# EsquematicoMicro.net
KiCad netlist of a schematic drawn in EAGLE
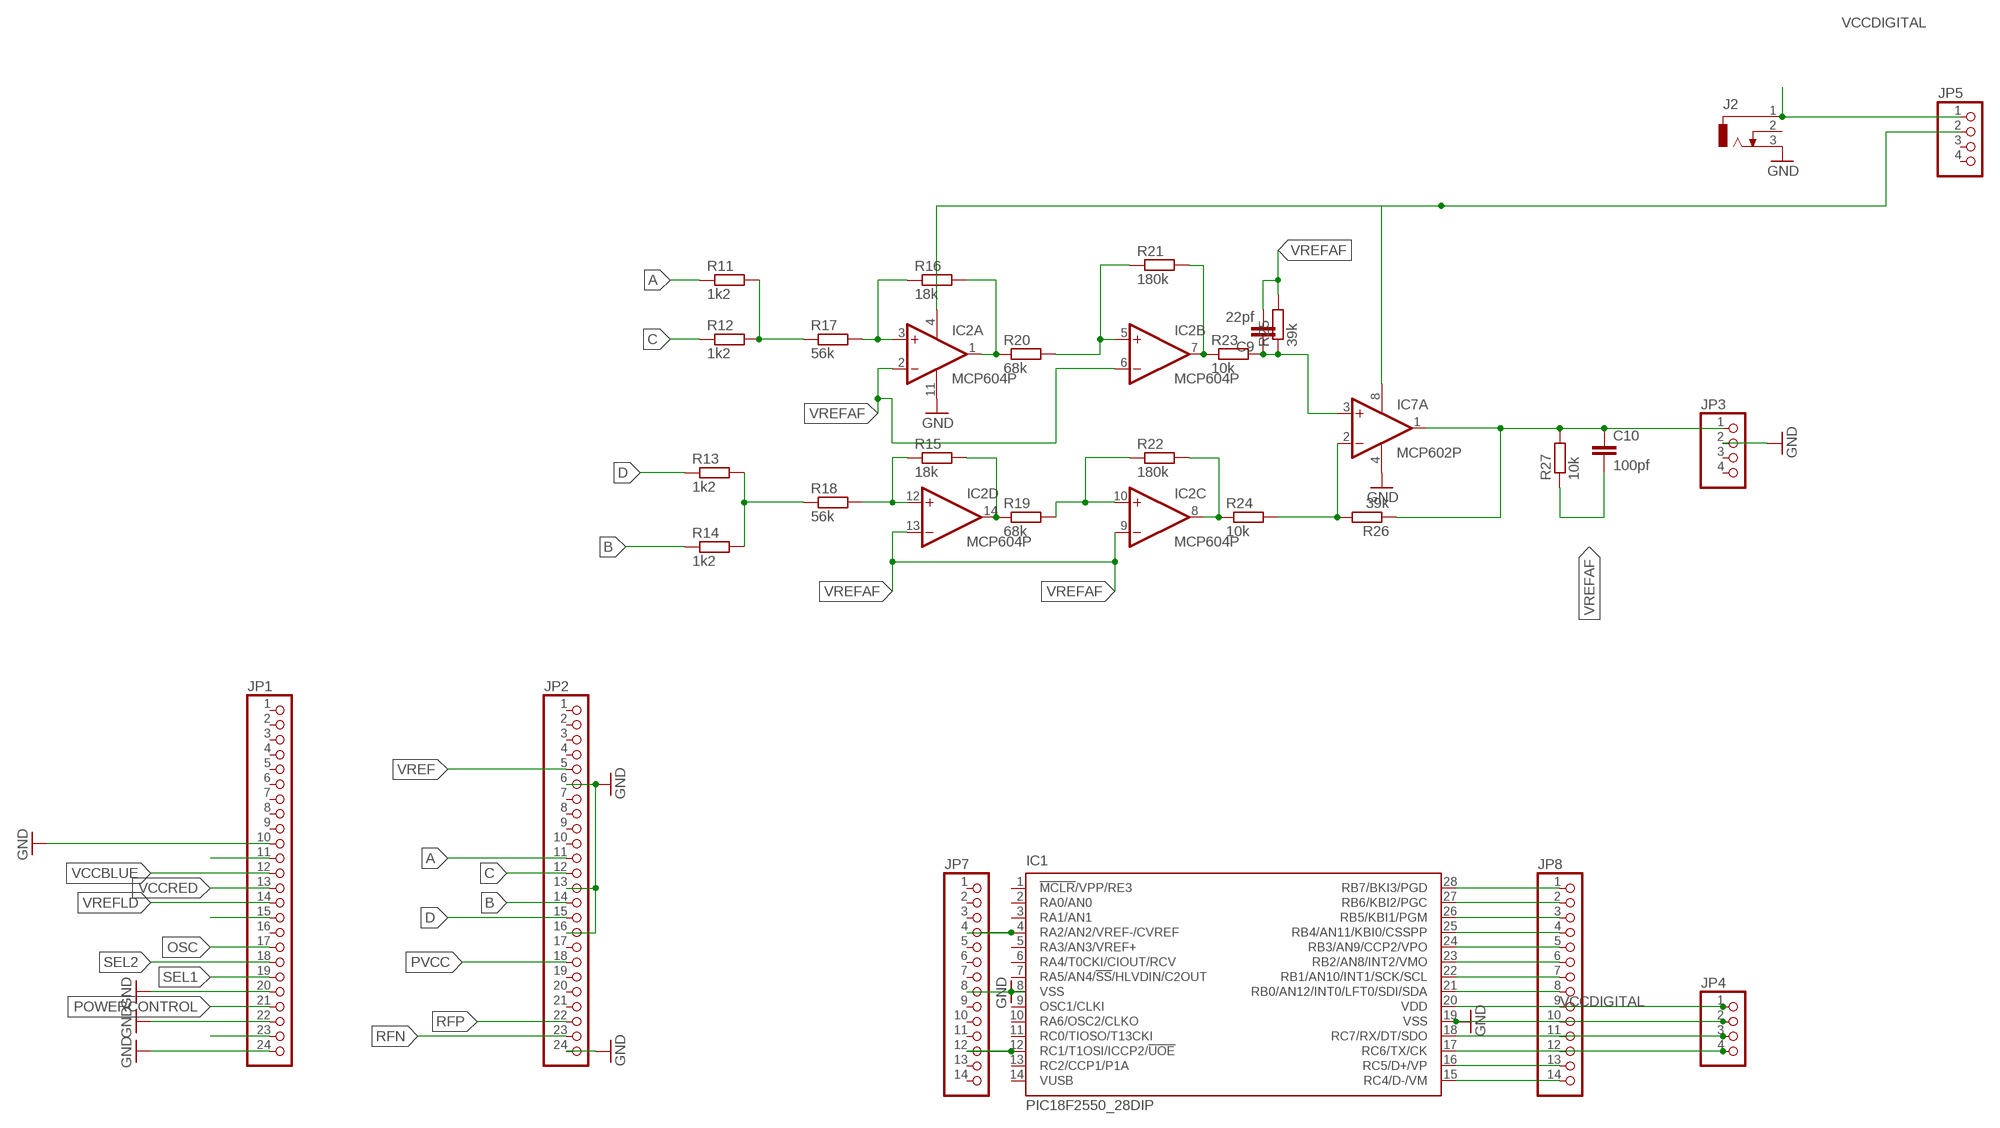
[diagram p0: schematic, sheet 1]

(export (version "E")
  (design (tool "Eeschema 10.0.6"))
  (components
    (comp (ref "C9")
      (value "22pf")
      (footprint "eagle-import:C025-025X050")
      (libsource (lib "eagle-import") (part "C-EU025-025X050"))
    )
    (comp (ref "C10")
      (value "100pf")
      (footprint "eagle-import:C025-025X050")
      (libsource (lib "eagle-import") (part "C-EU025-025X050"))
    )
    (comp (ref "IC1")
      (value "PIC18F2550_28DIP")
      (footprint "eagle-import:DIL28-3")
      (fields (field (name "MF") "MICROCHIP") (field (name "MPN") "PIC18F2550-I/SP"))
      (libsource (lib "eagle-import") (part "PIC18F2_28DIP550"))
    )
    (comp (ref "IC2")
      (value "MCP604P")
      (footprint "eagle-import:DIL14")
      (libsource (lib "eagle-import") (part "MCP604P"))
    )
    (comp (ref "IC7")
      (value "MCP602P")
      (footprint "eagle-import:DIL08")
      (fields (field (name "SPICEPREFIX") "I"))
      (libsource (lib "eagle-import") (part "MCP602P"))
    )
    (comp (ref "J2")
      (value "DCJ0303")
      (footprint "eagle-import:DCJ0303")
      (libsource (lib "eagle-import") (part "DCJ0303"))
    )
    (comp (ref "JP1")
      (value "PINHD-1X24")
      (footprint "eagle-import:1X24")
      (libsource (lib "eagle-import") (part "PINHD-1X24"))
    )
    (comp (ref "JP2")
      (value "PINHD-1X24")
      (footprint "eagle-import:1X24")
      (libsource (lib "eagle-import") (part "PINHD-1X24"))
    )
    (comp (ref "JP3")
      (value "PINHD-1X4")
      (footprint "eagle-import:1X04")
      (libsource (lib "eagle-import") (part "PINHD-1X4"))
    )
    (comp (ref "JP4")
      (value "PINHD-1X4")
      (footprint "eagle-import:1X04")
      (libsource (lib "eagle-import") (part "PINHD-1X4"))
    )
    (comp (ref "JP5")
      (value "PINHD-1X4")
      (footprint "eagle-import:1X04")
      (libsource (lib "eagle-import") (part "PINHD-1X4"))
    )
    (comp (ref "JP7")
      (value "PINHD-1X14")
      (footprint "eagle-import:1X14")
      (libsource (lib "eagle-import") (part "PINHD-1X14"))
    )
    (comp (ref "JP8")
      (value "PINHD-1X14")
      (footprint "eagle-import:1X14")
      (libsource (lib "eagle-import") (part "PINHD-1X14"))
    )
    (comp (ref "R11")
      (value "1k2")
      (footprint "eagle-import:0204_5")
      (libsource (lib "eagle-import") (part "R-EU_0204/5"))
    )
    (comp (ref "R12")
      (value "1k2")
      (footprint "eagle-import:0204_5")
      (libsource (lib "eagle-import") (part "R-EU_0204/5"))
    )
    (comp (ref "R13")
      (value "1k2")
      (footprint "eagle-import:0204_5")
      (libsource (lib "eagle-import") (part "R-EU_0204/5"))
    )
    (comp (ref "R14")
      (value "1k2")
      (footprint "eagle-import:0204_5")
      (libsource (lib "eagle-import") (part "R-EU_0204/5"))
    )
    (comp (ref "R15")
      (value "18k")
      (footprint "eagle-import:0204_5")
      (libsource (lib "eagle-import") (part "R-EU_0204/5"))
    )
    (comp (ref "R16")
      (value "18k")
      (footprint "eagle-import:0204_5")
      (libsource (lib "eagle-import") (part "R-EU_0204/5"))
    )
    (comp (ref "R17")
      (value "56k")
      (footprint "eagle-import:0204_5")
      (libsource (lib "eagle-import") (part "R-EU_0204/5"))
    )
    (comp (ref "R18")
      (value "56k")
      (footprint "eagle-import:0204_5")
      (libsource (lib "eagle-import") (part "R-EU_0204/5"))
    )
    (comp (ref "R19")
      (value "68k")
      (footprint "eagle-import:0204_5")
      (libsource (lib "eagle-import") (part "R-EU_0204/5"))
    )
    (comp (ref "R20")
      (value "68k")
      (footprint "eagle-import:0204_5")
      (libsource (lib "eagle-import") (part "R-EU_0204/5"))
    )
    (comp (ref "R21")
      (value "180k")
      (footprint "eagle-import:0204_5")
      (libsource (lib "eagle-import") (part "R-EU_0204/5"))
    )
    (comp (ref "R22")
      (value "180k")
      (footprint "eagle-import:0204_5")
      (libsource (lib "eagle-import") (part "R-EU_0204/5"))
    )
    (comp (ref "R23")
      (value "10k")
      (footprint "eagle-import:0204_5")
      (libsource (lib "eagle-import") (part "R-EU_0204/5"))
    )
    (comp (ref "R24")
      (value "10k")
      (footprint "eagle-import:0204_5")
      (libsource (lib "eagle-import") (part "R-EU_0204/5"))
    )
    (comp (ref "R25")
      (value "39k")
      (footprint "eagle-import:0204_5")
      (libsource (lib "eagle-import") (part "R-EU_0204/5"))
    )
    (comp (ref "R26")
      (value "39k")
      (footprint "eagle-import:0204_5")
      (libsource (lib "eagle-import") (part "R-EU_0204/5"))
    )
    (comp (ref "R27")
      (value "10k")
      (footprint "eagle-import:0204_5")
      (libsource (lib "eagle-import") (part "R-EU_0204/5"))
    )
  )
  (nets
    (net (code "1") (name "/VCCDIGITAL") (class "Default")
      (node (ref "IC1") (pin "20") (pinfunction "VDD_20") (pintype "power_in"))
      (node (ref "J2") (pin "1") (pinfunction "1_1") (pintype "passive"))
      (node (ref "JP4") (pin "1") (pinfunction "1_1") (pintype "passive"))
      (node (ref "JP5") (pin "1") (pinfunction "1_1") (pintype "passive"))
      (node (ref "JP8") (pin "9") (pinfunction "9_9") (pintype "passive"))
    )
    (net (code "2") (name "A") (class "Default")
      (node (ref "JP2") (pin "11") (pinfunction "11_11") (pintype "passive"))
      (node (ref "R11") (pin "1") (pinfunction "1_1") (pintype "passive"))
    )
    (net (code "3") (name "B") (class "Default")
      (node (ref "JP2") (pin "14") (pinfunction "14_14") (pintype "passive"))
      (node (ref "R14") (pin "1") (pinfunction "1_1") (pintype "passive"))
    )
    (net (code "4") (name "C") (class "Default")
      (node (ref "JP2") (pin "12") (pinfunction "12_12") (pintype "passive"))
      (node (ref "R12") (pin "1") (pinfunction "1_1") (pintype "passive"))
    )
    (net (code "5") (name "D") (class "Default")
      (node (ref "JP2") (pin "15") (pinfunction "15_15") (pintype "passive"))
      (node (ref "R13") (pin "1") (pinfunction "1_1") (pintype "passive"))
    )
    (net (code "6") (name "GND") (class "Default")
      (node (ref "IC1") (pin "19") (pinfunction "VSS_19") (pintype "power_in"))
      (node (ref "IC1") (pin "8") (pinfunction "VSS_8") (pintype "power_in"))
      (node (ref "IC2") (pin "11") (pinfunction "V-_11") (pintype "power_in"))
      (node (ref "IC7") (pin "4") (pinfunction "V-_4") (pintype "power_in"))
      (node (ref "J2") (pin "3") (pinfunction "3_3") (pintype "passive"))
      (node (ref "JP1") (pin "10") (pinfunction "10_10") (pintype "passive"))
      (node (ref "JP1") (pin "20") (pinfunction "20_20") (pintype "passive"))
      (node (ref "JP1") (pin "22") (pinfunction "22_22") (pintype "passive"))
      (node (ref "JP1") (pin "24") (pinfunction "24_24") (pintype "passive"))
      (node (ref "JP2") (pin "13") (pinfunction "13_13") (pintype "passive"))
      (node (ref "JP2") (pin "16") (pinfunction "16_16") (pintype "passive"))
      (node (ref "JP2") (pin "24") (pinfunction "24_24") (pintype "passive"))
      (node (ref "JP2") (pin "6") (pinfunction "6_6") (pintype "passive"))
      (node (ref "JP3") (pin "2") (pinfunction "2_2") (pintype "passive"))
      (node (ref "JP4") (pin "2") (pinfunction "2_2") (pintype "passive"))
      (node (ref "JP7") (pin "8") (pinfunction "8_8") (pintype "passive"))
      (node (ref "JP8") (pin "10") (pinfunction "10_10") (pintype "passive"))
    )
    (net (code "7") (name "Net-(IC1-RA2{slash}AN2{slash}VREF-{slash}CVREF)") (class "Default")
      (node (ref "IC1") (pin "4") (pinfunction "RA2/AN2/VREF-/CVREF_4") (pintype "bidirectional"))
      (node (ref "JP7") (pin "4") (pinfunction "4_4") (pintype "passive"))
    )
    (net (code "8") (name "Net-(IC1-RB0{slash}AN12{slash}INT0{slash}LFT0{slash}SDI{slash}SDA)") (class "Default")
      (node (ref "IC1") (pin "21") (pinfunction "RB0/AN12/INT0/LFT0/SDI/SDA_21") (pintype "bidirectional"))
      (node (ref "JP8") (pin "8") (pinfunction "8_8") (pintype "passive"))
    )
    (net (code "9") (name "Net-(IC1-RB1{slash}AN10{slash}INT1{slash}SCK{slash}SCL)") (class "Default")
      (node (ref "IC1") (pin "22") (pinfunction "RB1/AN10/INT1/SCK/SCL_22") (pintype "bidirectional"))
      (node (ref "JP8") (pin "7") (pinfunction "7_7") (pintype "passive"))
    )
    (net (code "10") (name "Net-(IC1-RB2{slash}AN8{slash}INT2{slash}VMO)") (class "Default")
      (node (ref "IC1") (pin "23") (pinfunction "RB2/AN8/INT2/VMO_23") (pintype "bidirectional"))
      (node (ref "JP8") (pin "6") (pinfunction "6_6") (pintype "passive"))
    )
    (net (code "11") (name "Net-(IC1-RB3{slash}AN9{slash}CCP2{slash}VPO)") (class "Default")
      (node (ref "IC1") (pin "24") (pinfunction "RB3/AN9/CCP2/VPO_24") (pintype "bidirectional"))
      (node (ref "JP8") (pin "5") (pinfunction "5_5") (pintype "passive"))
    )
    (net (code "12") (name "Net-(IC1-RB4{slash}AN11{slash}KBI0{slash}CSSPP)") (class "Default")
      (node (ref "IC1") (pin "25") (pinfunction "RB4/AN11/KBI0/CSSPP_25") (pintype "bidirectional"))
      (node (ref "JP8") (pin "4") (pinfunction "4_4") (pintype "passive"))
    )
    (net (code "13") (name "Net-(IC1-RB5{slash}KBI1{slash}PGM)") (class "Default")
      (node (ref "IC1") (pin "26") (pinfunction "RB5/KBI1/PGM_26") (pintype "bidirectional"))
      (node (ref "JP8") (pin "3") (pinfunction "3_3") (pintype "passive"))
    )
    (net (code "14") (name "Net-(IC1-RB6{slash}KBI2{slash}PGC)") (class "Default")
      (node (ref "IC1") (pin "27") (pinfunction "RB6/KBI2/PGC_27") (pintype "bidirectional"))
      (node (ref "JP8") (pin "2") (pinfunction "2_2") (pintype "passive"))
    )
    (net (code "15") (name "Net-(IC1-RB7{slash}BKI3{slash}PGD)") (class "Default")
      (node (ref "IC1") (pin "28") (pinfunction "RB7/BKI3/PGD_28") (pintype "bidirectional"))
      (node (ref "JP8") (pin "1") (pinfunction "1_1") (pintype "passive"))
    )
    (net (code "16") (name "Net-(IC1-RC1{slash}T1OSI{slash}ICCP2{slash}~{UOE})") (class "Default")
      (node (ref "IC1") (pin "12") (pinfunction "RC1/T1OSI/ICCP2/~{UOE}_12") (pintype "bidirectional"))
      (node (ref "JP7") (pin "12") (pinfunction "12_12") (pintype "passive"))
    )
    (net (code "17") (name "Net-(IC1-RC4{slash}D-{slash}VM)") (class "Default")
      (node (ref "IC1") (pin "15") (pinfunction "RC4/D-/VM_15") (pintype "bidirectional"))
      (node (ref "JP8") (pin "14") (pinfunction "14_14") (pintype "passive"))
    )
    (net (code "18") (name "Net-(IC1-RC5{slash}D+{slash}VP)") (class "Default")
      (node (ref "IC1") (pin "16") (pinfunction "RC5/D+/VP_16") (pintype "bidirectional"))
      (node (ref "JP8") (pin "13") (pinfunction "13_13") (pintype "passive"))
    )
    (net (code "19") (name "Net-(IC1-RC6{slash}TX{slash}CK)") (class "Default")
      (node (ref "IC1") (pin "17") (pinfunction "RC6/TX/CK_17") (pintype "bidirectional"))
      (node (ref "JP4") (pin "4") (pinfunction "4_4") (pintype "passive"))
      (node (ref "JP8") (pin "12") (pinfunction "12_12") (pintype "passive"))
    )
    (net (code "20") (name "Net-(IC1-RC7{slash}RX{slash}DT{slash}SDO)") (class "Default")
      (node (ref "IC1") (pin "18") (pinfunction "RC7/RX/DT/SDO_18") (pintype "bidirectional"))
      (node (ref "JP4") (pin "3") (pinfunction "3_3") (pintype "passive"))
      (node (ref "JP8") (pin "11") (pinfunction "11_11") (pintype "passive"))
    )
    (net (code "21") (name "Net-(IC2A-+IN)") (class "Default")
      (node (ref "IC2") (pin "3") (pinfunction "+IN_3") (pintype "input"))
      (node (ref "R16") (pin "1") (pinfunction "1_1") (pintype "passive"))
      (node (ref "R17") (pin "2") (pinfunction "2_2") (pintype "passive"))
    )
    (net (code "22") (name "Net-(IC2A-OUT)") (class "Default")
      (node (ref "IC2") (pin "1") (pinfunction "OUT_1") (pintype "output"))
      (node (ref "R16") (pin "2") (pinfunction "2_2") (pintype "passive"))
      (node (ref "R20") (pin "1") (pinfunction "1_1") (pintype "passive"))
    )
    (net (code "23") (name "Net-(IC2B-+IN)") (class "Default")
      (node (ref "IC2") (pin "5") (pinfunction "+IN_5") (pintype "input"))
      (node (ref "R20") (pin "2") (pinfunction "2_2") (pintype "passive"))
      (node (ref "R21") (pin "1") (pinfunction "1_1") (pintype "passive"))
    )
    (net (code "24") (name "Net-(IC2B-OUT)") (class "Default")
      (node (ref "IC2") (pin "7") (pinfunction "OUT_7") (pintype "output"))
      (node (ref "R21") (pin "2") (pinfunction "2_2") (pintype "passive"))
      (node (ref "R23") (pin "1") (pinfunction "1_1") (pintype "passive"))
    )
    (net (code "25") (name "Net-(IC2C-+IN)") (class "Default")
      (node (ref "IC2") (pin "10") (pinfunction "+IN_10") (pintype "input"))
      (node (ref "R19") (pin "2") (pinfunction "2_2") (pintype "passive"))
      (node (ref "R22") (pin "1") (pinfunction "1_1") (pintype "passive"))
    )
    (net (code "26") (name "Net-(IC2C-OUT)") (class "Default")
      (node (ref "IC2") (pin "8") (pinfunction "OUT_8") (pintype "output"))
      (node (ref "R22") (pin "2") (pinfunction "2_2") (pintype "passive"))
      (node (ref "R24") (pin "1") (pinfunction "1_1") (pintype "passive"))
    )
    (net (code "27") (name "Net-(IC2D-+IN)") (class "Default")
      (node (ref "IC2") (pin "12") (pinfunction "+IN_12") (pintype "input"))
      (node (ref "R15") (pin "1") (pinfunction "1_1") (pintype "passive"))
      (node (ref "R18") (pin "2") (pinfunction "2_2") (pintype "passive"))
    )
    (net (code "28") (name "Net-(IC2D-OUT)") (class "Default")
      (node (ref "IC2") (pin "14") (pinfunction "OUT_14") (pintype "output"))
      (node (ref "R15") (pin "2") (pinfunction "2_2") (pintype "passive"))
      (node (ref "R19") (pin "1") (pinfunction "1_1") (pintype "passive"))
    )
    (net (code "29") (name "Net-(IC2E-V+)") (class "Default")
      (node (ref "IC2") (pin "4") (pinfunction "V+_4") (pintype "power_in"))
      (node (ref "IC7") (pin "8") (pinfunction "V+_8") (pintype "power_in"))
      (node (ref "JP5") (pin "2") (pinfunction "2_2") (pintype "passive"))
    )
    (net (code "30") (name "Net-(IC7A-+IN)") (class "Default")
      (node (ref "C9") (pin "1") (pinfunction "1_1") (pintype "passive"))
      (node (ref "IC7") (pin "3") (pinfunction "+IN_3") (pintype "input"))
      (node (ref "R23") (pin "2") (pinfunction "2_2") (pintype "passive"))
      (node (ref "R25") (pin "1") (pinfunction "1_1") (pintype "passive"))
    )
    (net (code "31") (name "Net-(IC7A--IN)") (class "Default")
      (node (ref "IC7") (pin "2") (pinfunction "-IN_2") (pintype "input"))
      (node (ref "R24") (pin "2") (pinfunction "2_2") (pintype "passive"))
      (node (ref "R26") (pin "2") (pinfunction "2_2") (pintype "passive"))
    )
    (net (code "32") (name "Net-(IC7A-OUT)") (class "Default")
      (node (ref "C10") (pin "1") (pinfunction "1_1") (pintype "passive"))
      (node (ref "IC7") (pin "1") (pinfunction "OUT_1") (pintype "output"))
      (node (ref "JP3") (pin "1") (pinfunction "1_1") (pintype "passive"))
      (node (ref "R26") (pin "1") (pinfunction "1_1") (pintype "passive"))
      (node (ref "R27") (pin "2") (pinfunction "2_2") (pintype "passive"))
    )
    (net (code "33") (name "Net-(R11-Pad2)") (class "Default")
      (node (ref "R11") (pin "2") (pinfunction "2_2") (pintype "passive"))
      (node (ref "R12") (pin "2") (pinfunction "2_2") (pintype "passive"))
      (node (ref "R17") (pin "1") (pinfunction "1_1") (pintype "passive"))
    )
    (net (code "34") (name "Net-(R13-Pad2)") (class "Default")
      (node (ref "R13") (pin "2") (pinfunction "2_2") (pintype "passive"))
      (node (ref "R14") (pin "2") (pinfunction "2_2") (pintype "passive"))
      (node (ref "R18") (pin "1") (pinfunction "1_1") (pintype "passive"))
    )
    (net (code "35") (name "OSC") (class "Default")
      (node (ref "JP1") (pin "17") (pinfunction "17_17") (pintype "passive"))
    )
    (net (code "36") (name "POWERCONTROL") (class "Default")
      (node (ref "JP1") (pin "21") (pinfunction "21_21") (pintype "passive"))
    )
    (net (code "37") (name "PVCC") (class "Default")
      (node (ref "JP2") (pin "18") (pinfunction "18_18") (pintype "passive"))
    )
    (net (code "38") (name "RFN") (class "Default")
      (node (ref "JP2") (pin "23") (pinfunction "23_23") (pintype "passive"))
    )
    (net (code "39") (name "RFP") (class "Default")
      (node (ref "JP2") (pin "22") (pinfunction "22_22") (pintype "passive"))
    )
    (net (code "40") (name "SEL1") (class "Default")
      (node (ref "JP1") (pin "19") (pinfunction "19_19") (pintype "passive"))
    )
    (net (code "41") (name "SEL2") (class "Default")
      (node (ref "JP1") (pin "18") (pinfunction "18_18") (pintype "passive"))
    )
    (net (code "42") (name "VCCBLUE") (class "Default")
      (node (ref "JP1") (pin "12") (pinfunction "12_12") (pintype "passive"))
    )
    (net (code "43") (name "VCCRED") (class "Default")
      (node (ref "JP1") (pin "13") (pinfunction "13_13") (pintype "passive"))
    )
    (net (code "44") (name "VREF") (class "Default")
      (node (ref "JP2") (pin "5") (pinfunction "5_5") (pintype "passive"))
    )
    (net (code "45") (name "VREFAF") (class "Default")
      (node (ref "C10") (pin "2") (pinfunction "2_2") (pintype "passive"))
      (node (ref "C9") (pin "2") (pinfunction "2_2") (pintype "passive"))
      (node (ref "IC2") (pin "13") (pinfunction "-IN_13") (pintype "input"))
      (node (ref "IC2") (pin "2") (pinfunction "-IN_2") (pintype "input"))
      (node (ref "IC2") (pin "6") (pinfunction "-IN_6") (pintype "input"))
      (node (ref "IC2") (pin "9") (pinfunction "-IN_9") (pintype "input"))
      (node (ref "R25") (pin "2") (pinfunction "2_2") (pintype "passive"))
      (node (ref "R27") (pin "1") (pinfunction "1_1") (pintype "passive"))
    )
    (net (code "46") (name "VREFLD") (class "Default")
      (node (ref "JP1") (pin "14") (pinfunction "14_14") (pintype "passive"))
    )
    (net (code "47") (name "unconnected-(IC1-OSC1{slash}CLKI-Pad9)") (class "Default")
      (node (ref "IC1") (pin "9") (pinfunction "OSC1/CLKI_9") (pintype "input"))
    )
    (net (code "48") (name "unconnected-(IC1-RA0{slash}AN0-Pad2)") (class "Default")
      (node (ref "IC1") (pin "2") (pinfunction "RA0/AN0_2") (pintype "bidirectional"))
    )
    (net (code "49") (name "unconnected-(IC1-RA1{slash}AN1-Pad3)") (class "Default")
      (node (ref "IC1") (pin "3") (pinfunction "RA1/AN1_3") (pintype "bidirectional"))
    )
    (net (code "50") (name "unconnected-(IC1-RA3{slash}AN3{slash}VREF+-Pad5)") (class "Default")
      (node (ref "IC1") (pin "5") (pinfunction "RA3/AN3/VREF+_5") (pintype "bidirectional"))
    )
    (net (code "51") (name "unconnected-(IC1-RA4{slash}T0CKI{slash}CIOUT{slash}RCV-Pad6)") (class "Default")
      (node (ref "IC1") (pin "6") (pinfunction "RA4/T0CKI/CIOUT/RCV_6") (pintype "bidirectional"))
    )
    (net (code "52") (name "unconnected-(IC1-RA5{slash}AN4{slash}~{SS}{slash}HLVDIN{slash}C2OUT-Pad7)") (class "Default")
      (node (ref "IC1") (pin "7") (pinfunction "RA5/AN4/~{SS}/HLVDIN/C2OUT_7") (pintype "bidirectional"))
    )
    (net (code "53") (name "unconnected-(IC1-RA6{slash}OSC2{slash}CLKO-Pad10)") (class "Default")
      (node (ref "IC1") (pin "10") (pinfunction "RA6/OSC2/CLKO_10") (pintype "output"))
    )
    (net (code "54") (name "unconnected-(IC1-RC0{slash}TIOSO{slash}T13CKI-Pad11)") (class "Default")
      (node (ref "IC1") (pin "11") (pinfunction "RC0/TIOSO/T13CKI_11") (pintype "bidirectional"))
    )
    (net (code "55") (name "unconnected-(IC1-RC2{slash}CCP1{slash}P1A-Pad13)") (class "Default")
      (node (ref "IC1") (pin "13") (pinfunction "RC2/CCP1/P1A_13") (pintype "bidirectional"))
    )
    (net (code "56") (name "unconnected-(IC1-VUSB-Pad14)") (class "Default")
      (node (ref "IC1") (pin "14") (pinfunction "VUSB_14") (pintype "bidirectional"))
    )
    (net (code "57") (name "unconnected-(IC1-~{MCLR}{slash}VPP{slash}RE3-Pad1)") (class "Default")
      (node (ref "IC1") (pin "1") (pinfunction "~{MCLR}/VPP/RE3_1") (pintype "input"))
    )
    (net (code "58") (name "unconnected-(J2-Pad2)") (class "Default")
      (node (ref "J2") (pin "2") (pinfunction "2_2") (pintype "passive"))
    )
    (net (code "59") (name "unconnected-(JP1-Pad1)") (class "Default")
      (node (ref "JP1") (pin "1") (pinfunction "1_1") (pintype "passive"))
    )
    (net (code "60") (name "unconnected-(JP1-Pad2)") (class "Default")
      (node (ref "JP1") (pin "2") (pinfunction "2_2") (pintype "passive"))
    )
    (net (code "61") (name "unconnected-(JP1-Pad3)") (class "Default")
      (node (ref "JP1") (pin "3") (pinfunction "3_3") (pintype "passive"))
    )
    (net (code "62") (name "unconnected-(JP1-Pad4)") (class "Default")
      (node (ref "JP1") (pin "4") (pinfunction "4_4") (pintype "passive"))
    )
    (net (code "63") (name "unconnected-(JP1-Pad5)") (class "Default")
      (node (ref "JP1") (pin "5") (pinfunction "5_5") (pintype "passive"))
    )
    (net (code "64") (name "unconnected-(JP1-Pad6)") (class "Default")
      (node (ref "JP1") (pin "6") (pinfunction "6_6") (pintype "passive"))
    )
    (net (code "65") (name "unconnected-(JP1-Pad7)") (class "Default")
      (node (ref "JP1") (pin "7") (pinfunction "7_7") (pintype "passive"))
    )
    (net (code "66") (name "unconnected-(JP1-Pad8)") (class "Default")
      (node (ref "JP1") (pin "8") (pinfunction "8_8") (pintype "passive"))
    )
    (net (code "67") (name "unconnected-(JP1-Pad9)") (class "Default")
      (node (ref "JP1") (pin "9") (pinfunction "9_9") (pintype "passive"))
    )
    (net (code "68") (name "unconnected-(JP1-Pad11)") (class "Default")
      (node (ref "JP1") (pin "11") (pinfunction "11_11") (pintype "passive"))
    )
    (net (code "69") (name "unconnected-(JP1-Pad15)") (class "Default")
      (node (ref "JP1") (pin "15") (pinfunction "15_15") (pintype "passive"))
    )
    (net (code "70") (name "unconnected-(JP1-Pad16)") (class "Default")
      (node (ref "JP1") (pin "16") (pinfunction "16_16") (pintype "passive"))
    )
    (net (code "71") (name "unconnected-(JP1-Pad23)") (class "Default")
      (node (ref "JP1") (pin "23") (pinfunction "23_23") (pintype "passive"))
    )
    (net (code "72") (name "unconnected-(JP2-Pad1)") (class "Default")
      (node (ref "JP2") (pin "1") (pinfunction "1_1") (pintype "passive"))
    )
    (net (code "73") (name "unconnected-(JP2-Pad2)") (class "Default")
      (node (ref "JP2") (pin "2") (pinfunction "2_2") (pintype "passive"))
    )
    (net (code "74") (name "unconnected-(JP2-Pad3)") (class "Default")
      (node (ref "JP2") (pin "3") (pinfunction "3_3") (pintype "passive"))
    )
    (net (code "75") (name "unconnected-(JP2-Pad4)") (class "Default")
      (node (ref "JP2") (pin "4") (pinfunction "4_4") (pintype "passive"))
    )
    (net (code "76") (name "unconnected-(JP2-Pad7)") (class "Default")
      (node (ref "JP2") (pin "7") (pinfunction "7_7") (pintype "passive"))
    )
    (net (code "77") (name "unconnected-(JP2-Pad8)") (class "Default")
      (node (ref "JP2") (pin "8") (pinfunction "8_8") (pintype "passive"))
    )
    (net (code "78") (name "unconnected-(JP2-Pad9)") (class "Default")
      (node (ref "JP2") (pin "9") (pinfunction "9_9") (pintype "passive"))
    )
    (net (code "79") (name "unconnected-(JP2-Pad10)") (class "Default")
      (node (ref "JP2") (pin "10") (pinfunction "10_10") (pintype "passive"))
    )
    (net (code "80") (name "unconnected-(JP2-Pad17)") (class "Default")
      (node (ref "JP2") (pin "17") (pinfunction "17_17") (pintype "passive"))
    )
    (net (code "81") (name "unconnected-(JP2-Pad19)") (class "Default")
      (node (ref "JP2") (pin "19") (pinfunction "19_19") (pintype "passive"))
    )
    (net (code "82") (name "unconnected-(JP2-Pad20)") (class "Default")
      (node (ref "JP2") (pin "20") (pinfunction "20_20") (pintype "passive"))
    )
    (net (code "83") (name "unconnected-(JP2-Pad21)") (class "Default")
      (node (ref "JP2") (pin "21") (pinfunction "21_21") (pintype "passive"))
    )
    (net (code "84") (name "unconnected-(JP3-Pad3)") (class "Default")
      (node (ref "JP3") (pin "3") (pinfunction "3_3") (pintype "passive"))
    )
    (net (code "85") (name "unconnected-(JP3-Pad4)") (class "Default")
      (node (ref "JP3") (pin "4") (pinfunction "4_4") (pintype "passive"))
    )
    (net (code "86") (name "unconnected-(JP5-Pad3)") (class "Default")
      (node (ref "JP5") (pin "3") (pinfunction "3_3") (pintype "passive"))
    )
    (net (code "87") (name "unconnected-(JP5-Pad4)") (class "Default")
      (node (ref "JP5") (pin "4") (pinfunction "4_4") (pintype "passive"))
    )
    (net (code "88") (name "unconnected-(JP7-Pad1)") (class "Default")
      (node (ref "JP7") (pin "1") (pinfunction "1_1") (pintype "passive"))
    )
    (net (code "89") (name "unconnected-(JP7-Pad2)") (class "Default")
      (node (ref "JP7") (pin "2") (pinfunction "2_2") (pintype "passive"))
    )
    (net (code "90") (name "unconnected-(JP7-Pad3)") (class "Default")
      (node (ref "JP7") (pin "3") (pinfunction "3_3") (pintype "passive"))
    )
    (net (code "91") (name "unconnected-(JP7-Pad5)") (class "Default")
      (node (ref "JP7") (pin "5") (pinfunction "5_5") (pintype "passive"))
    )
    (net (code "92") (name "unconnected-(JP7-Pad6)") (class "Default")
      (node (ref "JP7") (pin "6") (pinfunction "6_6") (pintype "passive"))
    )
    (net (code "93") (name "unconnected-(JP7-Pad7)") (class "Default")
      (node (ref "JP7") (pin "7") (pinfunction "7_7") (pintype "passive"))
    )
    (net (code "94") (name "unconnected-(JP7-Pad9)") (class "Default")
      (node (ref "JP7") (pin "9") (pinfunction "9_9") (pintype "passive"))
    )
    (net (code "95") (name "unconnected-(JP7-Pad10)") (class "Default")
      (node (ref "JP7") (pin "10") (pinfunction "10_10") (pintype "passive"))
    )
    (net (code "96") (name "unconnected-(JP7-Pad11)") (class "Default")
      (node (ref "JP7") (pin "11") (pinfunction "11_11") (pintype "passive"))
    )
    (net (code "97") (name "unconnected-(JP7-Pad13)") (class "Default")
      (node (ref "JP7") (pin "13") (pinfunction "13_13") (pintype "passive"))
    )
    (net (code "98") (name "unconnected-(JP7-Pad14)") (class "Default")
      (node (ref "JP7") (pin "14") (pinfunction "14_14") (pintype "passive"))
    )
  )
)
